# fridge-p12f675.net
KiCad netlist of a schematic drawn in EAGLE
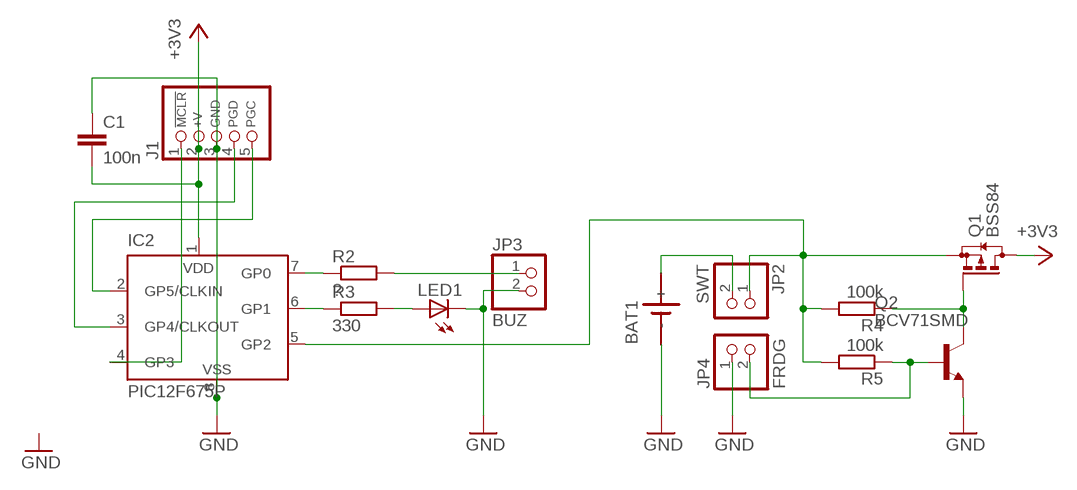
[diagram p0: schematic, sheet 1]

(export (version "E")
  (design (tool "Eeschema 10.0.6"))
  (components
    (comp (ref "BAT1")
      (value "SN2032")
      (footprint "eagle-import:SN2032")
      (libsource (lib "eagle-import") (part "SN2032"))
    )
    (comp (ref "C1")
      (value "100n")
      (footprint "eagle-import:C0805K")
      (libsource (lib "eagle-import") (part "C-EUC0805K"))
    )
    (comp (ref "IC2")
      (value "PIC12F675P")
      (footprint "eagle-import:DIL8")
      (fields (field (name "MF") "MICROCHIP") (field (name "MPN") "PIC12F675-E/P"))
      (libsource (lib "eagle-import") (part "PIC12F6P75"))
    )
    (comp (ref "J1")
      (value "CON_HEADER_PRG_PIC_ICSP0.1INCH_A")
      (footprint "eagle-import:HEADER_PRG_1X05")
      (libsource (lib "eagle-import") (part "CON_HEADER_PRG_PIC_ICSP0.1INCH_A"))
    )
    (comp (ref "JP2")
      (value "SWT")
      (footprint "eagle-import:1X02")
      (libsource (lib "eagle-import") (part "PINHD-1X2"))
    )
    (comp (ref "JP3")
      (value "BUZ")
      (footprint "eagle-import:1X02")
      (libsource (lib "eagle-import") (part "PINHD-1X2"))
    )
    (comp (ref "JP4")
      (value "FRDG")
      (footprint "eagle-import:1X02")
      (libsource (lib "eagle-import") (part "PINHD-1X2"))
    )
    (comp (ref "LED1")
      (value "LEDCHIPLED_0805")
      (footprint "eagle-import:CHIPLED_0805")
      (libsource (lib "eagle-import") (part "LEDCHIPLED_0805"))
    )
    (comp (ref "Q1")
      (value "BSS84")
      (footprint "eagle-import:SOT23")
      (libsource (lib "eagle-import") (part "BSS84"))
    )
    (comp (ref "Q2")
      (value "BCV71SMD")
      (footprint "eagle-import:SOT23-BEC")
      (libsource (lib "eagle-import") (part "BCV71SMD"))
    )
    (comp (ref "R2")
      (value "?")
      (footprint "eagle-import:R0805")
      (libsource (lib "eagle-import") (part "R-EU_R0805"))
    )
    (comp (ref "R3")
      (value "330")
      (footprint "eagle-import:R0805")
      (libsource (lib "eagle-import") (part "R-EU_R0805"))
    )
    (comp (ref "R4")
      (value "100k")
      (footprint "eagle-import:R0805")
      (libsource (lib "eagle-import") (part "R-EU_R0805"))
    )
    (comp (ref "R5")
      (value "100k")
      (footprint "eagle-import:R0805")
      (libsource (lib "eagle-import") (part "R-EU_R0805"))
    )
  )
  (nets
    (net (code "1") (name "+3V3") (class "Default")
      (node (ref "C1") (pin "2") (pinfunction "2_2") (pintype "passive"))
      (node (ref "IC2") (pin "1") (pinfunction "VDD_1") (pintype "power_in"))
      (node (ref "J1") (pin "2") (pinfunction "+V_2") (pintype "passive"))
      (node (ref "Q1") (pin "3") (pinfunction "D_3") (pintype "passive"))
    )
    (net (code "2") (name "GND") (class "Default")
      (node (ref "BAT1") (pin "-") (pinfunction "-_-") (pintype "passive"))
      (node (ref "C1") (pin "1") (pinfunction "1_1") (pintype "passive"))
      (node (ref "IC2") (pin "8") (pinfunction "VSS_8") (pintype "power_in"))
      (node (ref "J1") (pin "3") (pinfunction "GND_3") (pintype "passive"))
      (node (ref "JP3") (pin "2") (pinfunction "2_2") (pintype "passive"))
      (node (ref "JP4") (pin "1") (pinfunction "1_1") (pintype "passive"))
      (node (ref "LED1") (pin "C") (pinfunction "C_C") (pintype "passive"))
      (node (ref "Q2") (pin "E") (pinfunction "E_E") (pintype "passive"))
    )
    (net (code "3") (name "Net-(BAT1-Pad+)") (class "Default")
      (node (ref "BAT1") (pin "+") (pinfunction "+_+") (pintype "passive"))
      (node (ref "JP2") (pin "2") (pinfunction "2_2") (pintype "passive"))
    )
    (net (code "4") (name "Net-(IC2-GP0)") (class "Default")
      (node (ref "IC2") (pin "7") (pinfunction "GP0_7") (pintype "bidirectional"))
      (node (ref "R2") (pin "1") (pinfunction "1_1") (pintype "passive"))
    )
    (net (code "5") (name "Net-(IC2-GP1)") (class "Default")
      (node (ref "IC2") (pin "6") (pinfunction "GP1_6") (pintype "bidirectional"))
      (node (ref "R3") (pin "1") (pinfunction "1_1") (pintype "passive"))
    )
    (net (code "6") (name "Net-(IC2-GP2)") (class "Default")
      (node (ref "IC2") (pin "5") (pinfunction "GP2_5") (pintype "bidirectional"))
      (node (ref "JP2") (pin "1") (pinfunction "1_1") (pintype "passive"))
      (node (ref "Q1") (pin "2") (pinfunction "S_2") (pintype "passive"))
      (node (ref "R4") (pin "2") (pinfunction "2_2") (pintype "passive"))
      (node (ref "R5") (pin "2") (pinfunction "2_2") (pintype "passive"))
    )
    (net (code "7") (name "Net-(IC2-GP3)") (class "Default")
      (node (ref "IC2") (pin "4") (pinfunction "GP3_4") (pintype "input"))
      (node (ref "J1") (pin "1") (pinfunction "/MCLR_1") (pintype "passive"))
    )
    (net (code "8") (name "Net-(IC2-GP4{slash}CLKOUT)") (class "Default")
      (node (ref "IC2") (pin "3") (pinfunction "GP4/CLKOUT_3") (pintype "bidirectional"))
      (node (ref "J1") (pin "4") (pinfunction "PGD_4") (pintype "passive"))
    )
    (net (code "9") (name "Net-(IC2-GP5{slash}CLKIN)") (class "Default")
      (node (ref "IC2") (pin "2") (pinfunction "GP5/CLKIN_2") (pintype "bidirectional"))
      (node (ref "J1") (pin "5") (pinfunction "PGC_5") (pintype "passive"))
    )
    (net (code "10") (name "Net-(JP3-Pad1)") (class "Default")
      (node (ref "JP3") (pin "1") (pinfunction "1_1") (pintype "passive"))
      (node (ref "R2") (pin "2") (pinfunction "2_2") (pintype "passive"))
    )
    (net (code "11") (name "Net-(JP4-Pad2)") (class "Default")
      (node (ref "JP4") (pin "2") (pinfunction "2_2") (pintype "passive"))
      (node (ref "Q2") (pin "B") (pinfunction "B_B") (pintype "passive"))
      (node (ref "R5") (pin "1") (pinfunction "1_1") (pintype "passive"))
    )
    (net (code "12") (name "Net-(LED1-PadA)") (class "Default")
      (node (ref "LED1") (pin "A") (pinfunction "A_A") (pintype "passive"))
      (node (ref "R3") (pin "2") (pinfunction "2_2") (pintype "passive"))
    )
    (net (code "13") (name "Net-(Q1-G)") (class "Default")
      (node (ref "Q1") (pin "1") (pinfunction "G_1") (pintype "passive"))
      (node (ref "Q2") (pin "C") (pinfunction "C_C") (pintype "passive"))
      (node (ref "R4") (pin "1") (pinfunction "1_1") (pintype "passive"))
    )
  )
)
